# 04_LMS7002M_Misc.net
KiCad netlist of a schematic drawn in Altium Designer
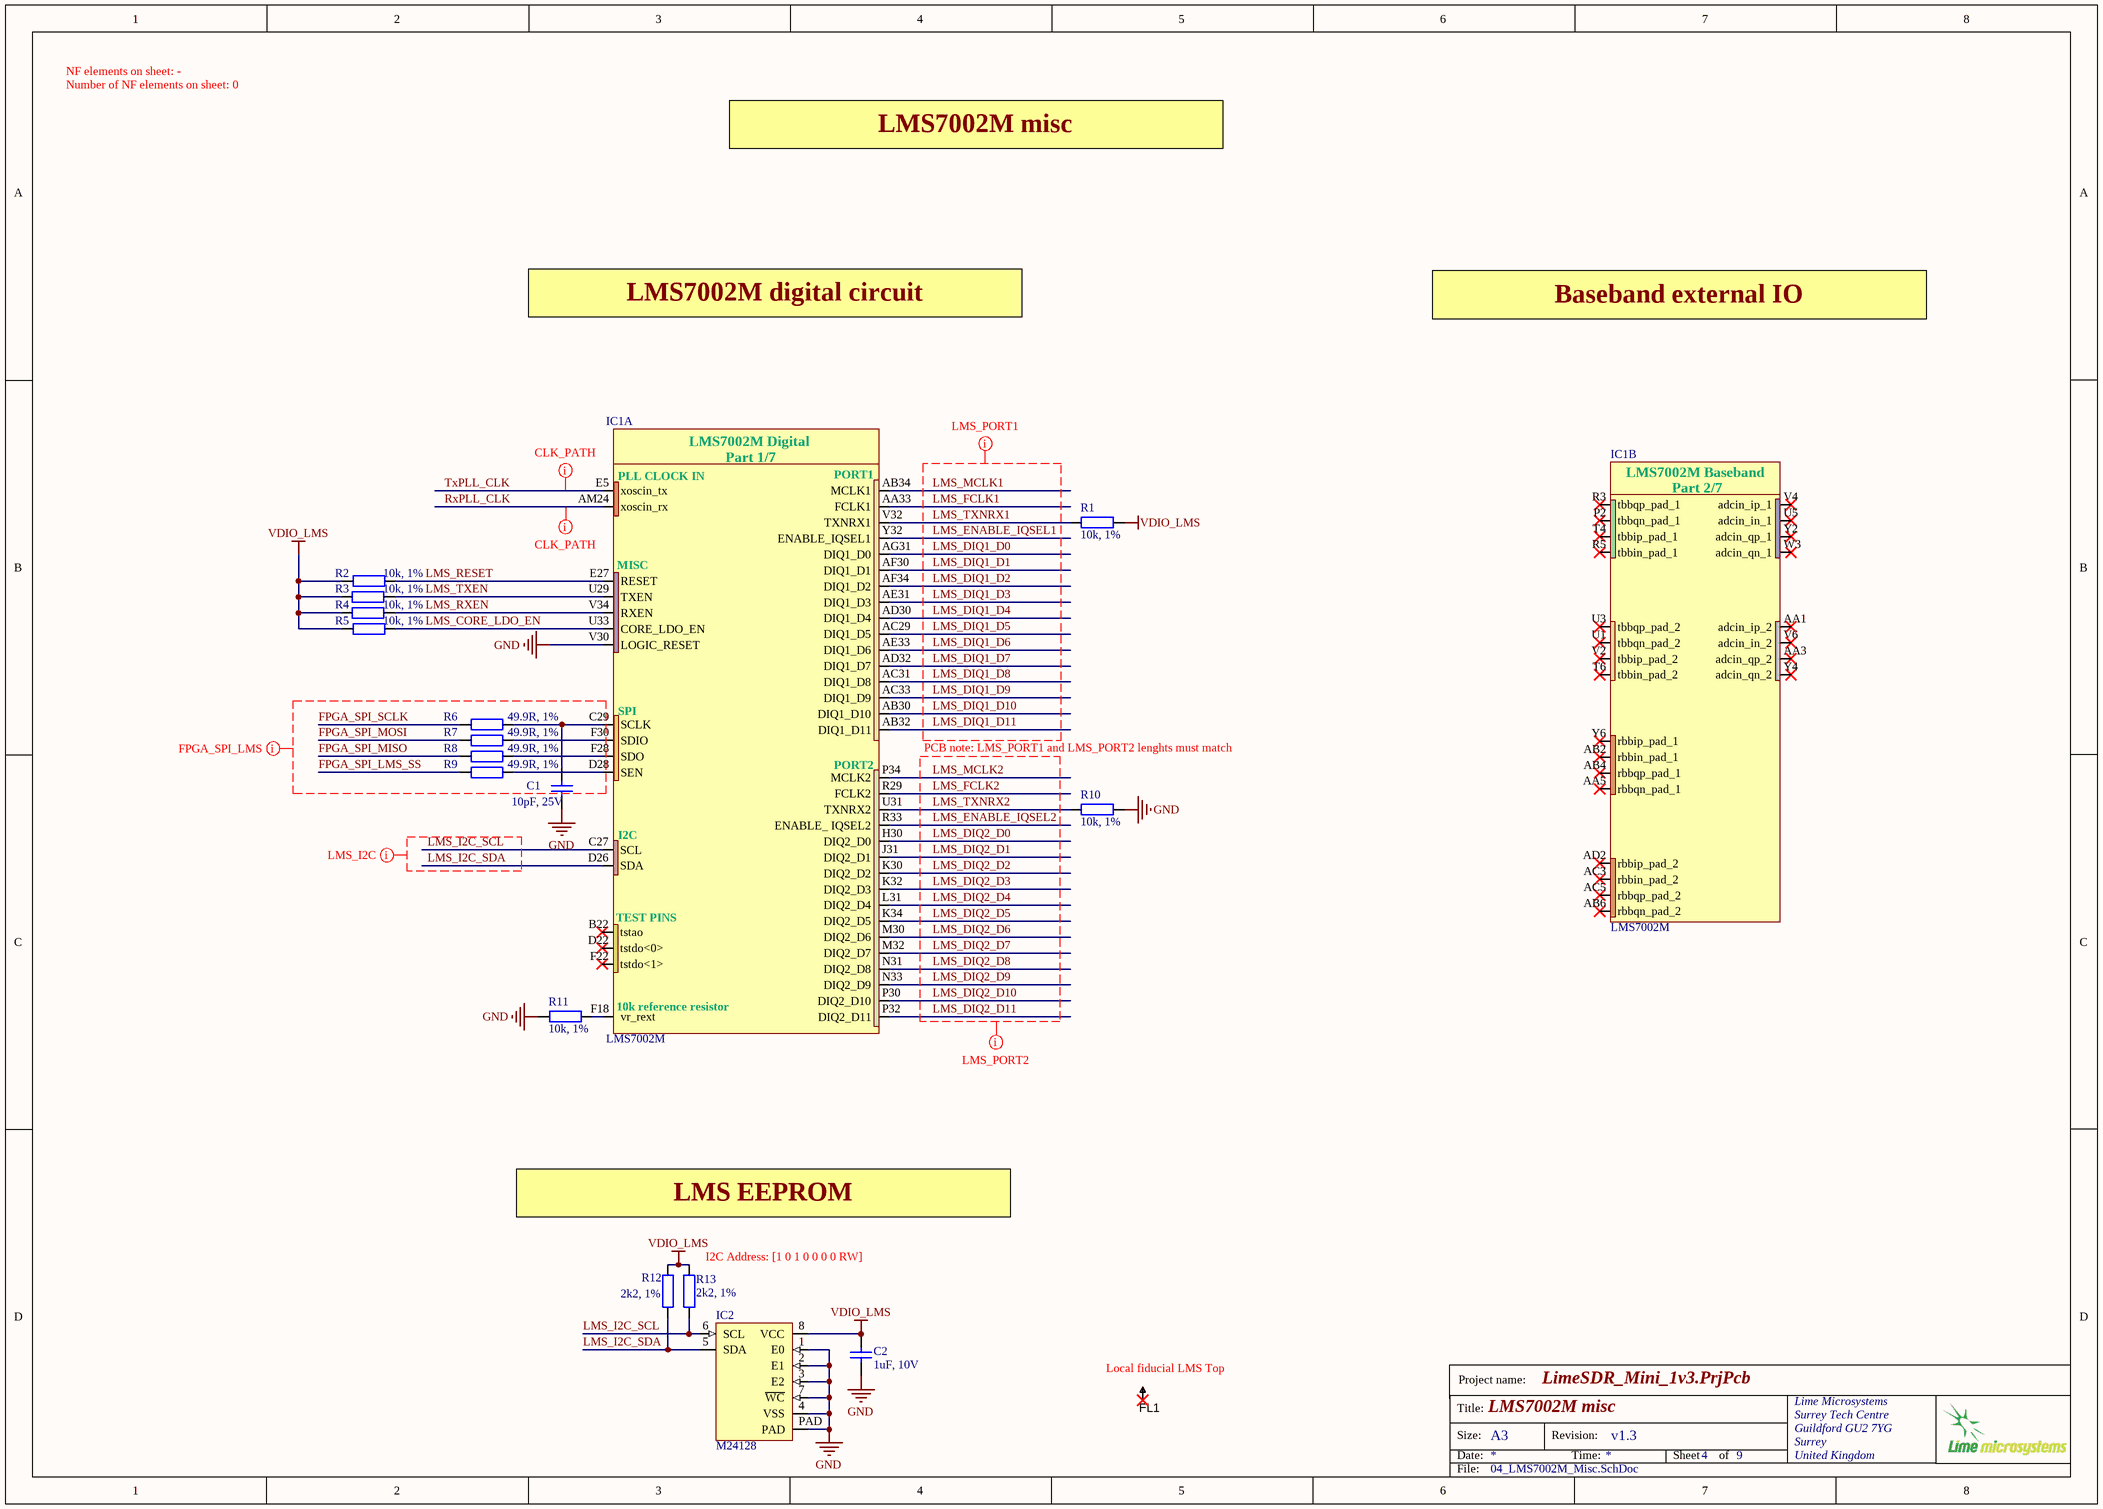
[diagram p0: 04_LMS7002M_Misc.SchDoc]

(export (version "E")
  (design (tool "Eeschema 10.0.6"))
  (components
    (comp (ref "C1")
      (value "10pF, 25V")
      (footprint "CAP0402")
      (fields (field (name "MANUFACTURER") "AVX"))
      (libsource (lib "LimeMicroAltiumLib_schLib") (part "Cap_0402"))
    )
    (comp (ref "C2")
      (value "1uF, 10V")
      (footprint "CAP0402")
      (fields (field (name "MANUFACTURER") "TDK"))
      (libsource (lib "LimeMicroAltiumLib_schLib") (part "Cap_0402"))
    )
    (comp (ref "FL1")
      (value "Fiducial")
      (footprint "Fiducial_local")
      (libsource (lib "VGTU_Altium_lib") (part "Fiducial"))
    )
    (comp (ref "IC1")
      (value "LMS7002M")
      (footprint "LMS7002M_v5")
      (description "Schematic symbol revision 3. Default footprint - 0.31mm pad")
      (fields (field (name "MANUFACTURER") "Lime Microsystems"))
      (libsource (lib "LimeMicroAltiumLib_schLib") (part "LMS7002Mr3"))
    )
    (comp (ref "IC2")
      (value "M24128")
      (footprint "M24128-DFMC6TG")
      (fields (field (name "MANUFACTURER") "STMicroelectronics"))
      (libsource (lib "LimeMicroAltiumLib_schLib") (part "M24128-DFMC6TG"))
    )
    (comp (ref "R1")
      (value "10k, 1%")
      (footprint "RES0402")
      (fields (field (name "MANUFACTURER") "Yageo") (field (name "TOLERANCE") "±1%"))
      (libsource (lib "LimeMicroAltiumLib_schLib") (part "Res_0402"))
    )
    (comp (ref "R2")
      (value "10k, 1%")
      (footprint "RES0402")
      (fields (field (name "MANUFACTURER") "Yageo") (field (name "TOLERANCE") "±1%"))
      (libsource (lib "LimeMicroAltiumLib_schLib") (part "Res_0402"))
    )
    (comp (ref "R3")
      (value "10k, 1%")
      (footprint "RES0402")
      (fields (field (name "MANUFACTURER") "Yageo") (field (name "TOLERANCE") "±1%"))
      (libsource (lib "LimeMicroAltiumLib_schLib") (part "Res_0402"))
    )
    (comp (ref "R4")
      (value "10k, 1%")
      (footprint "RES0402")
      (fields (field (name "MANUFACTURER") "Yageo") (field (name "TOLERANCE") "±1%"))
      (libsource (lib "LimeMicroAltiumLib_schLib") (part "Res_0402"))
    )
    (comp (ref "R5")
      (value "10k, 1%")
      (footprint "RES0402")
      (fields (field (name "MANUFACTURER") "Yageo") (field (name "TOLERANCE") "±1%"))
      (libsource (lib "LimeMicroAltiumLib_schLib") (part "Res_0402"))
    )
    (comp (ref "R6")
      (value "49.9R, 1%")
      (footprint "RES0402")
      (fields
        (field (name "TOLERANCE") "±1%")
        (field (name "MANUFACTURER") "Samsung Electro-Mechanics America, Inc.")
      )
      (libsource (lib "LimeMicroAltiumLib_schLib") (part "Res_0402"))
    )
    (comp (ref "R7")
      (value "49.9R, 1%")
      (footprint "RES0402")
      (fields
        (field (name "TOLERANCE") "±1%")
        (field (name "MANUFACTURER") "Samsung Electro-Mechanics America, Inc.")
      )
      (libsource (lib "LimeMicroAltiumLib_schLib") (part "Res_0402"))
    )
    (comp (ref "R8")
      (value "49.9R, 1%")
      (footprint "RES0402")
      (fields
        (field (name "TOLERANCE") "±1%")
        (field (name "MANUFACTURER") "Samsung Electro-Mechanics America, Inc.")
      )
      (libsource (lib "LimeMicroAltiumLib_schLib") (part "Res_0402"))
    )
    (comp (ref "R9")
      (value "49.9R, 1%")
      (footprint "RES0402")
      (fields
        (field (name "TOLERANCE") "±1%")
        (field (name "MANUFACTURER") "Samsung Electro-Mechanics America, Inc.")
      )
      (libsource (lib "LimeMicroAltiumLib_schLib") (part "Res_0402"))
    )
    (comp (ref "R10")
      (value "10k, 1%")
      (footprint "RES0402")
      (fields (field (name "MANUFACTURER") "Yageo") (field (name "TOLERANCE") "±1%"))
      (libsource (lib "LimeMicroAltiumLib_schLib") (part "Res_0402"))
    )
    (comp (ref "R11")
      (value "10k, 1%")
      (footprint "RES0402")
      (fields (field (name "MANUFACTURER") "Yageo") (field (name "TOLERANCE") "±1%"))
      (libsource (lib "LimeMicroAltiumLib_schLib") (part "Res_0402"))
    )
    (comp (ref "R12")
      (value "2k2, 1%")
      (footprint "RES0402")
      (fields (field (name "MANUFACTURER") "Stackpole Electronics Inc") (field (name "TOLERANCE") "±1%"))
      (libsource (lib "LimeMicroAltiumLib_schLib") (part "Res_0402"))
    )
    (comp (ref "R13")
      (value "2k2, 1%")
      (footprint "RES0402")
      (fields (field (name "MANUFACTURER") "Stackpole Electronics Inc") (field (name "TOLERANCE") "±1%"))
      (libsource (lib "LimeMicroAltiumLib_schLib") (part "Res_0402"))
    )
  )
  (nets
    (net (code "1") (name "/FPGA_SPI_LMS_SS") (class "Default")
      (node (ref "R9") (pin "2") (pinfunction "2_2") (pintype "passive"))
    )
    (net (code "2") (name "/FPGA_SPI_MISO") (class "Default")
      (node (ref "R8") (pin "2") (pinfunction "2_2") (pintype "passive"))
    )
    (net (code "3") (name "/FPGA_SPI_MOSI") (class "Default")
      (node (ref "R7") (pin "2") (pinfunction "2_2") (pintype "passive"))
    )
    (net (code "4") (name "/FPGA_SPI_SCLK") (class "Default")
      (node (ref "R6") (pin "2") (pinfunction "2_2") (pintype "passive"))
    )
    (net (code "5") (name "/LMS_CORE_LDO_EN") (class "Default")
      (node (ref "IC1") (pin "U33") (pinfunction "CORE_LDO_EN_U33") (pintype "passive"))
      (node (ref "R5") (pin "1") (pinfunction "1_1") (pintype "passive"))
    )
    (net (code "6") (name "/LMS_DIQ1_D0") (class "Default")
      (node (ref "IC1") (pin "AG31") (pinfunction "DIQ1_D0_AG31") (pintype "passive"))
    )
    (net (code "7") (name "/LMS_DIQ1_D1") (class "Default")
      (node (ref "IC1") (pin "AF30") (pinfunction "DIQ1_D1_AF30") (pintype "passive"))
    )
    (net (code "8") (name "/LMS_DIQ1_D2") (class "Default")
      (node (ref "IC1") (pin "AF34") (pinfunction "DIQ1_D2_AF34") (pintype "passive"))
    )
    (net (code "9") (name "/LMS_DIQ1_D3") (class "Default")
      (node (ref "IC1") (pin "AE31") (pinfunction "DIQ1_D3_AE31") (pintype "passive"))
    )
    (net (code "10") (name "/LMS_DIQ1_D4") (class "Default")
      (node (ref "IC1") (pin "AD30") (pinfunction "DIQ1_D4_AD30") (pintype "passive"))
    )
    (net (code "11") (name "/LMS_DIQ1_D5") (class "Default")
      (node (ref "IC1") (pin "AC29") (pinfunction "DIQ1_D5_AC29") (pintype "passive"))
    )
    (net (code "12") (name "/LMS_DIQ1_D6") (class "Default")
      (node (ref "IC1") (pin "AE33") (pinfunction "DIQ1_D6_AE33") (pintype "passive"))
    )
    (net (code "13") (name "/LMS_DIQ1_D7") (class "Default")
      (node (ref "IC1") (pin "AD32") (pinfunction "DIQ1_D7_AD32") (pintype "passive"))
    )
    (net (code "14") (name "/LMS_DIQ1_D8") (class "Default")
      (node (ref "IC1") (pin "AC31") (pinfunction "DIQ1_D8_AC31") (pintype "passive"))
    )
    (net (code "15") (name "/LMS_DIQ1_D9") (class "Default")
      (node (ref "IC1") (pin "AC33") (pinfunction "DIQ1_D9_AC33") (pintype "passive"))
    )
    (net (code "16") (name "/LMS_DIQ1_D10") (class "Default")
      (node (ref "IC1") (pin "AB30") (pinfunction "DIQ1_D10_AB30") (pintype "passive"))
    )
    (net (code "17") (name "/LMS_DIQ1_D11") (class "Default")
      (node (ref "IC1") (pin "AB32") (pinfunction "DIQ1_D11_AB32") (pintype "passive"))
    )
    (net (code "18") (name "/LMS_DIQ2_D0") (class "Default")
      (node (ref "IC1") (pin "H30") (pinfunction "DIQ2_D0_H30") (pintype "passive"))
    )
    (net (code "19") (name "/LMS_DIQ2_D1") (class "Default")
      (node (ref "IC1") (pin "J31") (pinfunction "DIQ2_D1_J31") (pintype "passive"))
    )
    (net (code "20") (name "/LMS_DIQ2_D2") (class "Default")
      (node (ref "IC1") (pin "K30") (pinfunction "DIQ2_D2_K30") (pintype "passive"))
    )
    (net (code "21") (name "/LMS_DIQ2_D3") (class "Default")
      (node (ref "IC1") (pin "K32") (pinfunction "DIQ2_D3_K32") (pintype "passive"))
    )
    (net (code "22") (name "/LMS_DIQ2_D4") (class "Default")
      (node (ref "IC1") (pin "L31") (pinfunction "DIQ2_D4_L31") (pintype "passive"))
    )
    (net (code "23") (name "/LMS_DIQ2_D5") (class "Default")
      (node (ref "IC1") (pin "K34") (pinfunction "DIQ2_D5_K34") (pintype "passive"))
    )
    (net (code "24") (name "/LMS_DIQ2_D6") (class "Default")
      (node (ref "IC1") (pin "M30") (pinfunction "DIQ2_D6_M30") (pintype "passive"))
    )
    (net (code "25") (name "/LMS_DIQ2_D7") (class "Default")
      (node (ref "IC1") (pin "M32") (pinfunction "DIQ2_D7_M32") (pintype "passive"))
    )
    (net (code "26") (name "/LMS_DIQ2_D8") (class "Default")
      (node (ref "IC1") (pin "N31") (pinfunction "DIQ2_D8_N31") (pintype "passive"))
    )
    (net (code "27") (name "/LMS_DIQ2_D9") (class "Default")
      (node (ref "IC1") (pin "N33") (pinfunction "DIQ2_D9_N33") (pintype "passive"))
    )
    (net (code "28") (name "/LMS_DIQ2_D10") (class "Default")
      (node (ref "IC1") (pin "P30") (pinfunction "DIQ2_D10_P30") (pintype "passive"))
    )
    (net (code "29") (name "/LMS_DIQ2_D11") (class "Default")
      (node (ref "IC1") (pin "P32") (pinfunction "DIQ2_D11_P32") (pintype "passive"))
    )
    (net (code "30") (name "/LMS_ENABLE_IQSEL1") (class "Default")
      (node (ref "IC1") (pin "Y32") (pinfunction "ENABLE_IQSEL1_Y32") (pintype "passive"))
    )
    (net (code "31") (name "/LMS_ENABLE_IQSEL2") (class "Default")
      (node (ref "IC1") (pin "R33") (pinfunction "ENABLE__IQSEL2_R33") (pintype "passive"))
    )
    (net (code "32") (name "/LMS_FCLK1") (class "Default")
      (node (ref "IC1") (pin "AA33") (pinfunction "FCLK1_AA33") (pintype "passive"))
    )
    (net (code "33") (name "/LMS_FCLK2") (class "Default")
      (node (ref "IC1") (pin "R29") (pinfunction "FCLK2_R29") (pintype "passive"))
    )
    (net (code "34") (name "/LMS_I2C_SCL") (class "Default")
      (node (ref "IC1") (pin "C27") (pinfunction "SCL_C27") (pintype "passive"))
      (node (ref "IC2") (pin "6") (pinfunction "SCL_6") (pintype "input"))
      (node (ref "R13") (pin "2") (pinfunction "2_2") (pintype "passive"))
    )
    (net (code "35") (name "/LMS_I2C_SDA") (class "Default")
      (node (ref "IC1") (pin "D26") (pinfunction "SDA_D26") (pintype "passive"))
      (node (ref "IC2") (pin "5") (pinfunction "SDA_5") (pintype "bidirectional"))
      (node (ref "R12") (pin "2") (pinfunction "2_2") (pintype "passive"))
    )
    (net (code "36") (name "/LMS_MCLK1") (class "Default")
      (node (ref "IC1") (pin "AB34") (pinfunction "MCLK1_AB34") (pintype "passive"))
    )
    (net (code "37") (name "/LMS_MCLK2") (class "Default")
      (node (ref "IC1") (pin "P34") (pinfunction "MCLK2_P34") (pintype "passive"))
    )
    (net (code "38") (name "/LMS_RESET") (class "Default")
      (node (ref "IC1") (pin "E27") (pinfunction "RESET_E27") (pintype "passive"))
      (node (ref "R2") (pin "1") (pinfunction "1_1") (pintype "passive"))
    )
    (net (code "39") (name "/LMS_RXEN") (class "Default")
      (node (ref "IC1") (pin "V34") (pinfunction "RXEN_V34") (pintype "passive"))
      (node (ref "R4") (pin "2") (pinfunction "2_2") (pintype "passive"))
    )
    (net (code "40") (name "/LMS_TXEN") (class "Default")
      (node (ref "IC1") (pin "U29") (pinfunction "TXEN_U29") (pintype "passive"))
      (node (ref "R3") (pin "2") (pinfunction "2_2") (pintype "passive"))
    )
    (net (code "41") (name "/LMS_TXNRX1") (class "Default")
      (node (ref "IC1") (pin "V32") (pinfunction "TXNRX1_V32") (pintype "passive"))
      (node (ref "R1") (pin "1") (pinfunction "1_1") (pintype "passive"))
    )
    (net (code "42") (name "/LMS_TXNRX2") (class "Default")
      (node (ref "IC1") (pin "U31") (pinfunction "TXNRX2_U31") (pintype "passive"))
      (node (ref "R10") (pin "1") (pinfunction "1_1") (pintype "passive"))
    )
    (net (code "43") (name "/RxPLL_CLK") (class "Default")
      (node (ref "IC1") (pin "AM24") (pinfunction "xoscin_rx_AM24") (pintype "passive"))
    )
    (net (code "44") (name "/TxPLL_CLK") (class "Default")
      (node (ref "IC1") (pin "E5") (pinfunction "xoscin_tx_E5") (pintype "passive"))
    )
    (net (code "45") (name "GND") (class "Default")
      (node (ref "C1") (pin "2") (pinfunction "2_2") (pintype "passive"))
      (node (ref "C2") (pin "2") (pinfunction "2_2") (pintype "passive"))
      (node (ref "IC1") (pin "V30") (pinfunction "LOGIC_RESET_V30") (pintype "passive"))
      (node (ref "IC2") (pin "1") (pinfunction "E0_1") (pintype "input"))
      (node (ref "IC2") (pin "2") (pinfunction "E1_2") (pintype "input"))
      (node (ref "IC2") (pin "3") (pinfunction "E2_3") (pintype "input"))
      (node (ref "IC2") (pin "4") (pinfunction "VSS_4") (pintype "power_in"))
      (node (ref "IC2") (pin "7") (pinfunction "~{WC}_7") (pintype "input"))
      (node (ref "IC2") (pin "PAD") (pinfunction "PAD_PAD") (pintype "power_in"))
      (node (ref "R10") (pin "2") (pinfunction "2_2") (pintype "passive"))
      (node (ref "R11") (pin "2") (pinfunction "2_2") (pintype "passive"))
    )
    (net (code "46") (name "Net-(IC1A-SCLK)") (class "Default")
      (node (ref "C1") (pin "1") (pinfunction "1_1") (pintype "passive"))
      (node (ref "IC1") (pin "C29") (pinfunction "SCLK_C29") (pintype "passive"))
      (node (ref "R6") (pin "1") (pinfunction "1_1") (pintype "passive"))
    )
    (net (code "47") (name "Net-(IC1A-SDIO)") (class "Default")
      (node (ref "IC1") (pin "F30") (pinfunction "SDIO_F30") (pintype "passive"))
      (node (ref "R7") (pin "1") (pinfunction "1_1") (pintype "passive"))
    )
    (net (code "48") (name "Net-(IC1A-SDO)") (class "Default")
      (node (ref "IC1") (pin "F28") (pinfunction "SDO_F28") (pintype "passive"))
      (node (ref "R8") (pin "1") (pinfunction "1_1") (pintype "passive"))
    )
    (net (code "49") (name "Net-(IC1A-SEN)") (class "Default")
      (node (ref "IC1") (pin "D28") (pinfunction "SEN_D28") (pintype "passive"))
      (node (ref "R9") (pin "1") (pinfunction "1_1") (pintype "passive"))
    )
    (net (code "50") (name "Net-(IC1A-vr_rext)") (class "Default")
      (node (ref "IC1") (pin "F18") (pinfunction "vr_rext_F18") (pintype "passive"))
      (node (ref "R11") (pin "1") (pinfunction "1_1") (pintype "passive"))
    )
    (net (code "51") (name "VDIO_LMS") (class "Default")
      (node (ref "C2") (pin "1") (pinfunction "1_1") (pintype "passive"))
      (node (ref "IC2") (pin "8") (pinfunction "VCC_8") (pintype "power_in"))
      (node (ref "R1") (pin "2") (pinfunction "2_2") (pintype "passive"))
      (node (ref "R12") (pin "1") (pinfunction "1_1") (pintype "passive"))
      (node (ref "R13") (pin "1") (pinfunction "1_1") (pintype "passive"))
      (node (ref "R2") (pin "2") (pinfunction "2_2") (pintype "passive"))
      (node (ref "R3") (pin "1") (pinfunction "1_1") (pintype "passive"))
      (node (ref "R4") (pin "1") (pinfunction "1_1") (pintype "passive"))
      (node (ref "R5") (pin "2") (pinfunction "2_2") (pintype "passive"))
    )
    (net (code "52") (name "unconnected-(FL1-Pad1)") (class "Default")
      (node (ref "FL1") (pin "1") (pintype "passive+no_connect"))
    )
    (net (code "53") (name "unconnected-(IC1A-tstao-PadB22)") (class "Default")
      (node (ref "IC1") (pin "B22") (pinfunction "tstao_B22") (pintype "passive+no_connect"))
    )
    (net (code "54") (name "unconnected-(IC1A-tstdo<0>-PadD22)") (class "Default")
      (node (ref "IC1") (pin "D22") (pinfunction "tstdo<0>_D22") (pintype "passive+no_connect"))
    )
    (net (code "55") (name "unconnected-(IC1A-tstdo<1>-PadF22)") (class "Default")
      (node (ref "IC1") (pin "F22") (pinfunction "tstdo<1>_F22") (pintype "passive+no_connect"))
    )
    (net (code "56") (name "unconnected-(IC1B-adcin_in_1-PadU5)") (class "Default")
      (node (ref "IC1") (pin "U5") (pinfunction "adcin_in_1_U5") (pintype "passive+no_connect"))
    )
    (net (code "57") (name "unconnected-(IC1B-adcin_in_2-PadV6)") (class "Default")
      (node (ref "IC1") (pin "V6") (pinfunction "adcin_in_2_V6") (pintype "passive+no_connect"))
    )
    (net (code "58") (name "unconnected-(IC1B-adcin_ip_1-PadV4)") (class "Default")
      (node (ref "IC1") (pin "V4") (pinfunction "adcin_ip_1_V4") (pintype "passive+no_connect"))
    )
    (net (code "59") (name "unconnected-(IC1B-adcin_ip_2-PadAA1)") (class "Default")
      (node (ref "IC1") (pin "AA1") (pinfunction "adcin_ip_2_AA1") (pintype "passive+no_connect"))
    )
    (net (code "60") (name "unconnected-(IC1B-adcin_qn_1-PadW3)") (class "Default")
      (node (ref "IC1") (pin "W3") (pinfunction "adcin_qn_1_W3") (pintype "passive+no_connect"))
    )
    (net (code "61") (name "unconnected-(IC1B-adcin_qn_2-PadY4)") (class "Default")
      (node (ref "IC1") (pin "Y4") (pinfunction "adcin_qn_2_Y4") (pintype "passive+no_connect"))
    )
    (net (code "62") (name "unconnected-(IC1B-adcin_qp_1-PadY2)") (class "Default")
      (node (ref "IC1") (pin "Y2") (pinfunction "adcin_qp_1_Y2") (pintype "passive+no_connect"))
    )
    (net (code "63") (name "unconnected-(IC1B-adcin_qp_2-PadAA3)") (class "Default")
      (node (ref "IC1") (pin "AA3") (pinfunction "adcin_qp_2_AA3") (pintype "passive+no_connect"))
    )
    (net (code "64") (name "unconnected-(IC1B-rbbin_pad_1-PadAB2)") (class "Default")
      (node (ref "IC1") (pin "AB2") (pinfunction "rbbin_pad_1_AB2") (pintype "passive+no_connect"))
    )
    (net (code "65") (name "unconnected-(IC1B-rbbin_pad_2-PadAC3)") (class "Default")
      (node (ref "IC1") (pin "AC3") (pinfunction "rbbin_pad_2_AC3") (pintype "passive+no_connect"))
    )
    (net (code "66") (name "unconnected-(IC1B-rbbip_pad_1-PadY6)") (class "Default")
      (node (ref "IC1") (pin "Y6") (pinfunction "rbbip_pad_1_Y6") (pintype "passive+no_connect"))
    )
    (net (code "67") (name "unconnected-(IC1B-rbbip_pad_2-PadAD2)") (class "Default")
      (node (ref "IC1") (pin "AD2") (pinfunction "rbbip_pad_2_AD2") (pintype "passive+no_connect"))
    )
    (net (code "68") (name "unconnected-(IC1B-rbbqn_pad_1-PadAA5)") (class "Default")
      (node (ref "IC1") (pin "AA5") (pinfunction "rbbqn_pad_1_AA5") (pintype "passive+no_connect"))
    )
    (net (code "69") (name "unconnected-(IC1B-rbbqn_pad_2-PadAB6)") (class "Default")
      (node (ref "IC1") (pin "AB6") (pinfunction "rbbqn_pad_2_AB6") (pintype "passive+no_connect"))
    )
    (net (code "70") (name "unconnected-(IC1B-rbbqp_pad_1-PadAB4)") (class "Default")
      (node (ref "IC1") (pin "AB4") (pinfunction "rbbqp_pad_1_AB4") (pintype "passive+no_connect"))
    )
    (net (code "71") (name "unconnected-(IC1B-rbbqp_pad_2-PadAC5)") (class "Default")
      (node (ref "IC1") (pin "AC5") (pinfunction "rbbqp_pad_2_AC5") (pintype "passive+no_connect"))
    )
    (net (code "72") (name "unconnected-(IC1B-tbbin_pad_1-PadR5)") (class "Default")
      (node (ref "IC1") (pin "R5") (pinfunction "tbbin_pad_1_R5") (pintype "passive+no_connect"))
    )
    (net (code "73") (name "unconnected-(IC1B-tbbin_pad_2-PadT6)") (class "Default")
      (node (ref "IC1") (pin "T6") (pinfunction "tbbin_pad_2_T6") (pintype "passive+no_connect"))
    )
    (net (code "74") (name "unconnected-(IC1B-tbbip_pad_1-PadT4)") (class "Default")
      (node (ref "IC1") (pin "T4") (pinfunction "tbbip_pad_1_T4") (pintype "passive+no_connect"))
    )
    (net (code "75") (name "unconnected-(IC1B-tbbip_pad_2-PadV2)") (class "Default")
      (node (ref "IC1") (pin "V2") (pinfunction "tbbip_pad_2_V2") (pintype "passive+no_connect"))
    )
    (net (code "76") (name "unconnected-(IC1B-tbbqn_pad_1-PadP2)") (class "Default")
      (node (ref "IC1") (pin "P2") (pinfunction "tbbqn_pad_1_P2") (pintype "passive+no_connect"))
    )
    (net (code "77") (name "unconnected-(IC1B-tbbqn_pad_2-PadU1)") (class "Default")
      (node (ref "IC1") (pin "U1") (pinfunction "tbbqn_pad_2_U1") (pintype "passive+no_connect"))
    )
    (net (code "78") (name "unconnected-(IC1B-tbbqp_pad_1-PadR3)") (class "Default")
      (node (ref "IC1") (pin "R3") (pinfunction "tbbqp_pad_1_R3") (pintype "passive+no_connect"))
    )
    (net (code "79") (name "unconnected-(IC1B-tbbqp_pad_2-PadU3)") (class "Default")
      (node (ref "IC1") (pin "U3") (pinfunction "tbbqp_pad_2_U3") (pintype "passive+no_connect"))
    )
  )
)
